# 06_LMS7002M_2_RF.net
KiCad netlist of a schematic drawn in Altium Designer
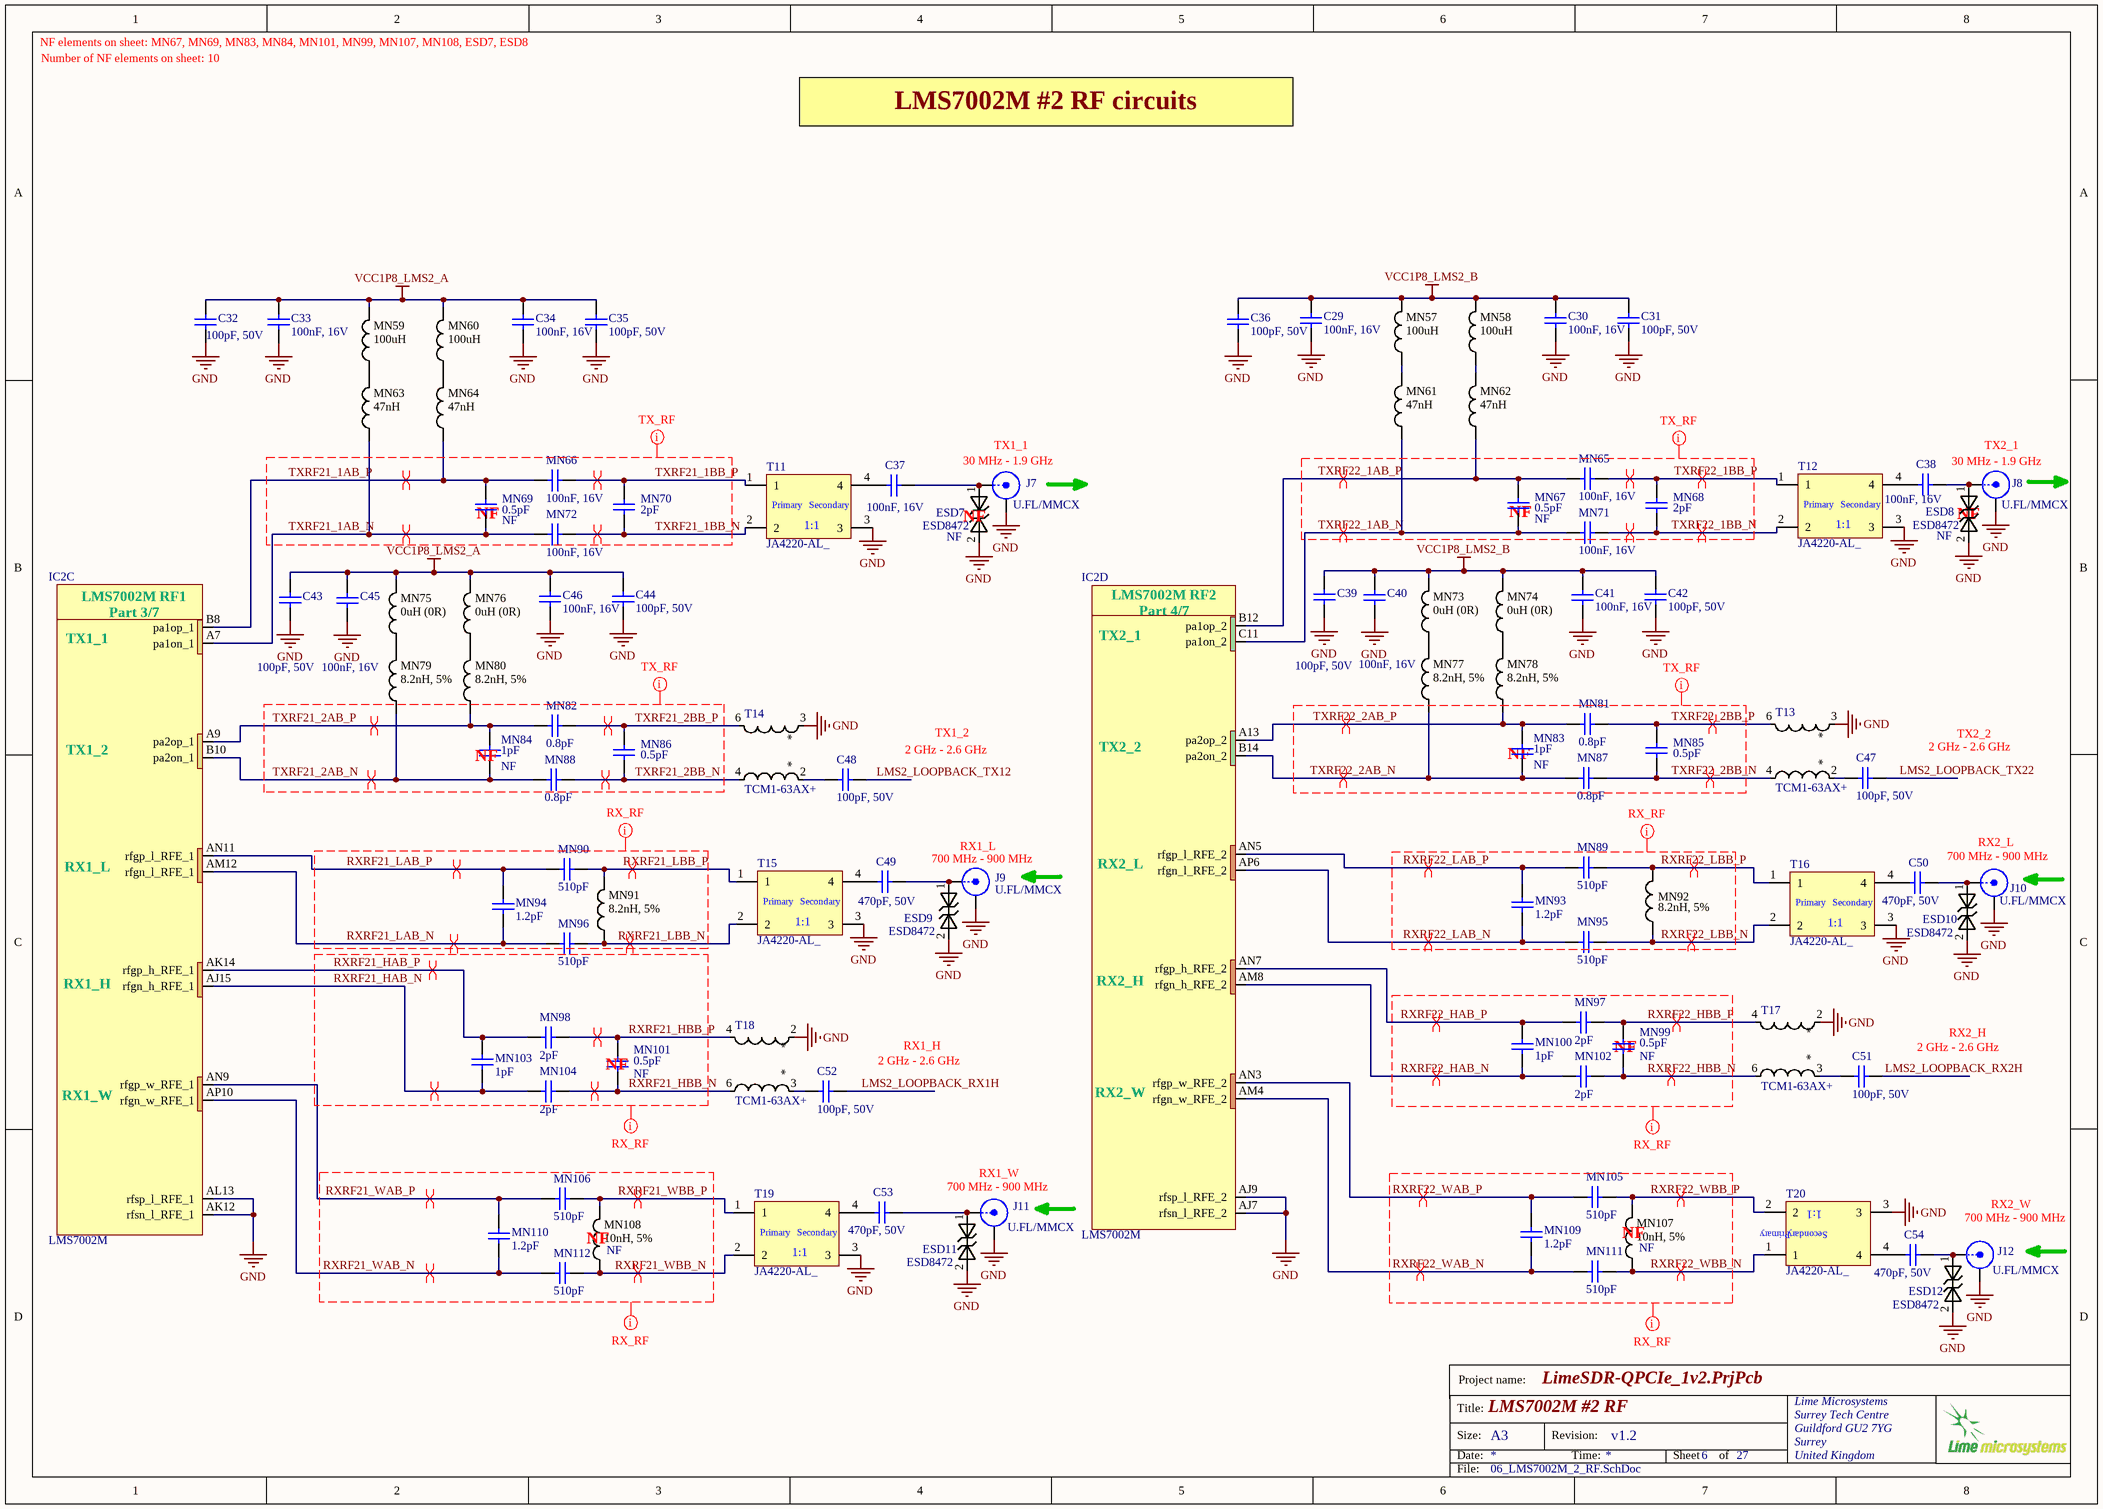
[diagram p0: 06_LMS7002M_2_RF.SchDoc]

(export (version "E")
  (design (tool "Eeschema 10.0.6"))
  (components
    (comp (ref "C29")
      (value "100nF, 16V")
      (footprint "CAP0402")
      (fields
        (field (name "MANUFACTURER") "Murata Electronics")
        (field (name "TOLERANCE") "10 %")
        (field (name "MANUFACTURER PART NUMBER") "GRM155R71C104KA88D")
      )
      (libsource (lib "LimeMicroAltiumLib_schLib") (part "Cap_0402"))
    )
    (comp (ref "C30")
      (value "100nF, 16V")
      (footprint "CAP0402")
      (fields
        (field (name "MANUFACTURER") "Murata Electronics")
        (field (name "TOLERANCE") "10 %")
        (field (name "MANUFACTURER PART NUMBER") "GRM155R71C104KA88D")
      )
      (libsource (lib "LimeMicroAltiumLib_schLib") (part "Cap_0402"))
    )
    (comp (ref "C31")
      (value "100pF, 50V")
      (footprint "CAP0402")
      (fields (field (name "MANUFACTURER") "Yageo") (field (name "TOLERANCE") "±5%"))
      (libsource (lib "LimeMicroAltiumLib_schLib") (part "Cap_0402"))
    )
    (comp (ref "C32")
      (value "100pF, 50V")
      (footprint "CAP0402")
      (fields (field (name "MANUFACTURER") "Yageo") (field (name "TOLERANCE") "±5%"))
      (libsource (lib "LimeMicroAltiumLib_schLib") (part "Cap_0402"))
    )
    (comp (ref "C33")
      (value "100nF, 16V")
      (footprint "CAP0402")
      (fields
        (field (name "MANUFACTURER") "Murata Electronics")
        (field (name "TOLERANCE") "10 %")
        (field (name "MANUFACTURER PART NUMBER") "GRM155R71C104KA88D")
      )
      (libsource (lib "LimeMicroAltiumLib_schLib") (part "Cap_0402"))
    )
    (comp (ref "C34")
      (value "100nF, 16V")
      (footprint "CAP0402")
      (fields
        (field (name "MANUFACTURER") "Murata Electronics")
        (field (name "TOLERANCE") "10 %")
        (field (name "MANUFACTURER PART NUMBER") "GRM155R71C104KA88D")
      )
      (libsource (lib "LimeMicroAltiumLib_schLib") (part "Cap_0402"))
    )
    (comp (ref "C35")
      (value "100pF, 50V")
      (footprint "CAP0402")
      (fields (field (name "MANUFACTURER") "Yageo") (field (name "TOLERANCE") "±5%"))
      (libsource (lib "LimeMicroAltiumLib_schLib") (part "Cap_0402"))
    )
    (comp (ref "C36")
      (value "100pF, 50V")
      (footprint "CAP0402")
      (fields (field (name "MANUFACTURER") "Yageo") (field (name "TOLERANCE") "±5%"))
      (libsource (lib "LimeMicroAltiumLib_schLib") (part "Cap_0402"))
    )
    (comp (ref "C37")
      (value "100nF, 16V")
      (footprint "CAP0402")
      (fields
        (field (name "MANUFACTURER") "Murata Electronics")
        (field (name "TOLERANCE") "10 %")
        (field (name "MANUFACTURER PART NUMBER") "GRM155R71C104KA88D")
      )
      (libsource (lib "LimeMicroAltiumLib_schLib") (part "Cap_0402"))
    )
    (comp (ref "C38")
      (value "100nF, 16V")
      (footprint "CAP0402")
      (fields
        (field (name "MANUFACTURER") "Murata Electronics")
        (field (name "TOLERANCE") "10 %")
        (field (name "MANUFACTURER PART NUMBER") "GRM155R71C104KA88D")
      )
      (libsource (lib "LimeMicroAltiumLib_schLib") (part "Cap_0402"))
    )
    (comp (ref "C39")
      (value "100pF, 50V")
      (footprint "CAP0402")
      (fields (field (name "MANUFACTURER") "Yageo") (field (name "TOLERANCE") "±5%"))
      (libsource (lib "LimeMicroAltiumLib_schLib") (part "Cap_0402"))
    )
    (comp (ref "C40")
      (value "100nF, 16V")
      (footprint "CAP0402")
      (fields
        (field (name "MANUFACTURER") "Murata Electronics")
        (field (name "TOLERANCE") "10 %")
        (field (name "MANUFACTURER PART NUMBER") "GRM155R71C104KA88D")
      )
      (libsource (lib "LimeMicroAltiumLib_schLib") (part "Cap_0402"))
    )
    (comp (ref "C41")
      (value "100nF, 16V")
      (footprint "CAP0402")
      (fields
        (field (name "MANUFACTURER") "Murata Electronics")
        (field (name "TOLERANCE") "10 %")
        (field (name "MANUFACTURER PART NUMBER") "GRM155R71C104KA88D")
      )
      (libsource (lib "LimeMicroAltiumLib_schLib") (part "Cap_0402"))
    )
    (comp (ref "C42")
      (value "100pF, 50V")
      (footprint "CAP0402")
      (fields (field (name "MANUFACTURER") "Yageo") (field (name "TOLERANCE") "±5%"))
      (libsource (lib "LimeMicroAltiumLib_schLib") (part "Cap_0402"))
    )
    (comp (ref "C43")
      (value "100pF, 50V")
      (footprint "CAP0402")
      (fields (field (name "MANUFACTURER") "Yageo") (field (name "TOLERANCE") "±5%"))
      (libsource (lib "LimeMicroAltiumLib_schLib") (part "Cap_0402"))
    )
    (comp (ref "C44")
      (value "100pF, 50V")
      (footprint "CAP0402")
      (fields (field (name "MANUFACTURER") "Yageo") (field (name "TOLERANCE") "±5%"))
      (libsource (lib "LimeMicroAltiumLib_schLib") (part "Cap_0402"))
    )
    (comp (ref "C45")
      (value "100nF, 16V")
      (footprint "CAP0402")
      (fields
        (field (name "MANUFACTURER") "Murata Electronics")
        (field (name "TOLERANCE") "10 %")
        (field (name "MANUFACTURER PART NUMBER") "GRM155R71C104KA88D")
      )
      (libsource (lib "LimeMicroAltiumLib_schLib") (part "Cap_0402"))
    )
    (comp (ref "C46")
      (value "100nF, 16V")
      (footprint "CAP0402")
      (fields
        (field (name "MANUFACTURER") "Murata Electronics")
        (field (name "TOLERANCE") "10 %")
        (field (name "MANUFACTURER PART NUMBER") "GRM155R71C104KA88D")
      )
      (libsource (lib "LimeMicroAltiumLib_schLib") (part "Cap_0402"))
    )
    (comp (ref "C47")
      (value "100pF, 50V")
      (footprint "CAP0402")
      (fields (field (name "TOLERANCE") "±5%") (field (name "MANUFACTURER") "Yageo"))
      (libsource (lib "LimeMicroAltiumLib_schLib") (part "Cap_0402"))
    )
    (comp (ref "C48")
      (value "100pF, 50V")
      (footprint "CAP0402")
      (fields (field (name "TOLERANCE") "±5%") (field (name "MANUFACTURER") "Yageo"))
      (libsource (lib "LimeMicroAltiumLib_schLib") (part "Cap_0402"))
    )
    (comp (ref "C49")
      (value "470pF, 50V")
      (footprint "CAP0402")
      (fields
        (field (name "MANUFACTURER PART NUMBER") "C1005C0G1H471J050BA")
        (field (name "TOLERANCE") "±5%")
        (field (name "MANUFACTURER") "TDK Corporation")
      )
      (libsource (lib "LimeMicroAltiumLib_schLib") (part "Cap_0402"))
    )
    (comp (ref "C50")
      (value "470pF, 50V")
      (footprint "CAP0402")
      (fields
        (field (name "MANUFACTURER PART NUMBER") "C1005C0G1H471J050BA")
        (field (name "TOLERANCE") "±5%")
        (field (name "MANUFACTURER") "TDK Corporation")
      )
      (libsource (lib "LimeMicroAltiumLib_schLib") (part "Cap_0402"))
    )
    (comp (ref "C51")
      (value "100pF, 50V")
      (footprint "CAP0402")
      (fields (field (name "TOLERANCE") "±5%") (field (name "MANUFACTURER") "Yageo"))
      (libsource (lib "LimeMicroAltiumLib_schLib") (part "Cap_0402"))
    )
    (comp (ref "C52")
      (value "100pF, 50V")
      (footprint "CAP0402")
      (fields (field (name "TOLERANCE") "±5%") (field (name "MANUFACTURER") "Yageo"))
      (libsource (lib "LimeMicroAltiumLib_schLib") (part "Cap_0402"))
    )
    (comp (ref "C53")
      (value "470pF, 50V")
      (footprint "CAP0402")
      (fields
        (field (name "MANUFACTURER PART NUMBER") "C1005C0G1H471J050BA")
        (field (name "TOLERANCE") "±5%")
        (field (name "MANUFACTURER") "TDK Corporation")
      )
      (libsource (lib "LimeMicroAltiumLib_schLib") (part "Cap_0402"))
    )
    (comp (ref "C54")
      (value "470pF, 50V")
      (footprint "CAP0402")
      (fields
        (field (name "MANUFACTURER PART NUMBER") "C1005C0G1H471J050BA")
        (field (name "TOLERANCE") "±5%")
        (field (name "MANUFACTURER") "TDK Corporation")
      )
      (libsource (lib "LimeMicroAltiumLib_schLib") (part "Cap_0402"))
    )
    (comp (ref "ESD7")
      (value "ESD8472")
      (footprint "ESD8472_X3DFN2")
      (fields
        (field (name "MANUFACTURER") "ON Semiconductor")
        (field (name "MANUFACTURER PART NUMBER") "ESD8472MUT5G")
        (field (name "ASSEMBLY INFO") "NF")
      )
      (libsource (lib "LimeMicroAltiumLib_schLib") (part "ESD8472"))
    )
    (comp (ref "ESD8")
      (value "ESD8472")
      (footprint "ESD8472_X3DFN2")
      (fields
        (field (name "MANUFACTURER") "ON Semiconductor")
        (field (name "MANUFACTURER PART NUMBER") "ESD8472MUT5G")
        (field (name "ASSEMBLY INFO") "NF")
      )
      (libsource (lib "LimeMicroAltiumLib_schLib") (part "ESD8472"))
    )
    (comp (ref "ESD9")
      (value "ESD8472")
      (footprint "ESD8472_X3DFN2")
      (fields
        (field (name "MANUFACTURER") "ON Semiconductor")
        (field (name "MANUFACTURER PART NUMBER") "ESD8472MUT5G")
      )
      (libsource (lib "LimeMicroAltiumLib_schLib") (part "ESD8472"))
    )
    (comp (ref "ESD10")
      (value "ESD8472")
      (footprint "ESD8472_X3DFN2")
      (fields
        (field (name "MANUFACTURER") "ON Semiconductor")
        (field (name "MANUFACTURER PART NUMBER") "ESD8472MUT5G")
      )
      (libsource (lib "LimeMicroAltiumLib_schLib") (part "ESD8472"))
    )
    (comp (ref "ESD11")
      (value "ESD8472")
      (footprint "ESD8472_X3DFN2")
      (fields
        (field (name "MANUFACTURER") "ON Semiconductor")
        (field (name "MANUFACTURER PART NUMBER") "ESD8472MUT5G")
      )
      (libsource (lib "LimeMicroAltiumLib_schLib") (part "ESD8472"))
    )
    (comp (ref "ESD12")
      (value "ESD8472")
      (footprint "ESD8472_X3DFN2")
      (fields
        (field (name "MANUFACTURER") "ON Semiconductor")
        (field (name "MANUFACTURER PART NUMBER") "ESD8472MUT5G")
      )
      (libsource (lib "LimeMicroAltiumLib_schLib") (part "ESD8472"))
    )
    (comp (ref "IC2")
      (value "LMS7002M")
      (footprint "LMS7002M_v4")
      (description "Schematic symbol revision 3. Default footprint - 0.31mm pad")
      (fields (field (name "MANUFACTURER") "Lime Microsystems"))
      (libsource (lib "LimeMicroAltiumLib_schLib") (part "LMS7002Mr3"))
    )
    (comp (ref "J7")
      (value "U.FL/MMCX")
      (footprint "MMCX_UFL_conn_u")
      (description "CONN UMC RCPT STR 50 OHM SMD")
      (fields (field (name "MANUFACTURER") "Molex, LLC"))
      (libsource (lib "LimeMicroAltiumLib_schLib") (part "RF_IF_connector"))
    )
    (comp (ref "J8")
      (value "U.FL/MMCX")
      (footprint "MMCX_UFL_conn_u")
      (description "CONN UMC RCPT STR 50 OHM SMD")
      (fields (field (name "MANUFACTURER") "Molex, LLC"))
      (libsource (lib "LimeMicroAltiumLib_schLib") (part "RF_IF_connector"))
    )
    (comp (ref "J9")
      (value "U.FL/MMCX")
      (footprint "MMCX_UFL_conn_u")
      (description "CONN UMC RCPT STR 50 OHM SMD")
      (fields (field (name "MANUFACTURER") "Molex, LLC"))
      (libsource (lib "LimeMicroAltiumLib_schLib") (part "RF_IF_connector"))
    )
    (comp (ref "J10")
      (value "U.FL/MMCX")
      (footprint "MMCX_UFL_conn_u")
      (description "CONN UMC RCPT STR 50 OHM SMD")
      (fields (field (name "MANUFACTURER") "Molex, LLC"))
      (libsource (lib "LimeMicroAltiumLib_schLib") (part "RF_IF_connector"))
    )
    (comp (ref "J11")
      (value "U.FL/MMCX")
      (footprint "MMCX_UFL_conn_u")
      (description "CONN UMC RCPT STR 50 OHM SMD")
      (fields (field (name "MANUFACTURER") "Molex, LLC"))
      (libsource (lib "LimeMicroAltiumLib_schLib") (part "RF_IF_connector"))
    )
    (comp (ref "J12")
      (value "U.FL/MMCX")
      (footprint "MMCX_UFL_conn_u")
      (description "CONN UMC RCPT STR 50 OHM SMD")
      (fields (field (name "MANUFACTURER") "Molex, LLC"))
      (libsource (lib "LimeMicroAltiumLib_schLib") (part "RF_IF_connector"))
    )
    (comp (ref "MN57")
      (value "100uH")
      (footprint "RES0805")
      (fields
        (field (name "TOLERANCE") "±10%")
        (field (name "MANUFACTURER") "TDK Corporation")
        (field (name "MANUFACTURER PART NUMBER") "MLF2012C101KT000")
      )
      (libsource (lib "LimeMicroAltiumLib_schLib") (part "Inductor_0603"))
    )
    (comp (ref "MN58")
      (value "100uH")
      (footprint "RES0805")
      (fields
        (field (name "TOLERANCE") "±10%")
        (field (name "MANUFACTURER") "TDK Corporation")
        (field (name "MANUFACTURER PART NUMBER") "MLF2012C101KT000")
      )
      (libsource (lib "LimeMicroAltiumLib_schLib") (part "Inductor_0603"))
    )
    (comp (ref "MN59")
      (value "100uH")
      (footprint "RES0805")
      (fields
        (field (name "TOLERANCE") "±10%")
        (field (name "MANUFACTURER") "TDK Corporation")
        (field (name "MANUFACTURER PART NUMBER") "MLF2012C101KT000")
      )
      (libsource (lib "LimeMicroAltiumLib_schLib") (part "Inductor_0603"))
    )
    (comp (ref "MN60")
      (value "100uH")
      (footprint "RES0805")
      (fields
        (field (name "TOLERANCE") "±10%")
        (field (name "MANUFACTURER") "TDK Corporation")
        (field (name "MANUFACTURER PART NUMBER") "MLF2012C101KT000")
      )
      (libsource (lib "LimeMicroAltiumLib_schLib") (part "Inductor_0603"))
    )
    (comp (ref "MN61")
      (value "47nH")
      (footprint "RES0402")
      (fields
        (field (name "MANUFACTURER") "COILCRAFT")
        (field (name "MANUFACTURER PART NUMBER") "0402HP-47NXJLU")
      )
      (libsource (lib "LimeMicroAltiumLib_schLib") (part "Inductor_0603"))
    )
    (comp (ref "MN62")
      (value "47nH")
      (footprint "RES0402")
      (fields
        (field (name "MANUFACTURER") "COILCRAFT")
        (field (name "MANUFACTURER PART NUMBER") "0402HP-47NXJLU")
      )
      (libsource (lib "LimeMicroAltiumLib_schLib") (part "Inductor_0603"))
    )
    (comp (ref "MN63")
      (value "47nH")
      (footprint "RES0402")
      (fields
        (field (name "MANUFACTURER") "COILCRAFT")
        (field (name "MANUFACTURER PART NUMBER") "0402HP-47NXJLU")
      )
      (libsource (lib "LimeMicroAltiumLib_schLib") (part "Inductor_0603"))
    )
    (comp (ref "MN64")
      (value "47nH")
      (footprint "RES0402")
      (fields
        (field (name "MANUFACTURER") "COILCRAFT")
        (field (name "MANUFACTURER PART NUMBER") "0402HP-47NXJLU")
      )
      (libsource (lib "LimeMicroAltiumLib_schLib") (part "Inductor_0603"))
    )
    (comp (ref "MN65")
      (value "100nF, 16V")
      (footprint "CAP0402")
      (fields
        (field (name "MANUFACTURER") "Murata Electronics")
        (field (name "TOLERANCE") "10 %")
        (field (name "MANUFACTURER PART NUMBER") "GRM155R71C104KA88D")
      )
      (libsource (lib "LimeMicroAltiumLib_schLib") (part "Cap_0402"))
    )
    (comp (ref "MN66")
      (value "100nF, 16V")
      (footprint "CAP0402")
      (fields
        (field (name "MANUFACTURER") "Murata Electronics")
        (field (name "TOLERANCE") "10 %")
        (field (name "MANUFACTURER PART NUMBER") "GRM155R71C104KA88D")
      )
      (libsource (lib "LimeMicroAltiumLib_schLib") (part "Cap_0402"))
    )
    (comp (ref "MN67")
      (value "0.5pF")
      (footprint "CAP0402")
      (fields
        (field (name "ASSEMBLY INFO") "NF")
        (field (name "TOLERANCE") "±0.25pF")
        (field (name "MANUFACTURER") "Yageo")
      )
      (libsource (lib "LimeMicroAltiumLib_schLib") (part "Cap_0402"))
    )
    (comp (ref "MN68")
      (value "2pF")
      (footprint "CAP0402")
      (fields (field (name "MANUFACTURER") "AVX"))
      (libsource (lib "LimeMicroAltiumLib_schLib") (part "Cap_0402"))
    )
    (comp (ref "MN69")
      (value "0.5pF")
      (footprint "CAP0402")
      (fields
        (field (name "ASSEMBLY INFO") "NF")
        (field (name "TOLERANCE") "±0.25pF")
        (field (name "MANUFACTURER") "Yageo")
      )
      (libsource (lib "LimeMicroAltiumLib_schLib") (part "Cap_0402"))
    )
    (comp (ref "MN70")
      (value "2pF")
      (footprint "CAP0402")
      (fields (field (name "MANUFACTURER") "AVX"))
      (libsource (lib "LimeMicroAltiumLib_schLib") (part "Cap_0402"))
    )
    (comp (ref "MN71")
      (value "100nF, 16V")
      (footprint "CAP0402")
      (fields
        (field (name "MANUFACTURER") "Murata Electronics")
        (field (name "TOLERANCE") "10 %")
        (field (name "MANUFACTURER PART NUMBER") "GRM155R71C104KA88D")
      )
      (libsource (lib "LimeMicroAltiumLib_schLib") (part "Cap_0402"))
    )
    (comp (ref "MN72")
      (value "100nF, 16V")
      (footprint "CAP0402")
      (fields
        (field (name "MANUFACTURER") "Murata Electronics")
        (field (name "TOLERANCE") "10 %")
        (field (name "MANUFACTURER PART NUMBER") "GRM155R71C104KA88D")
      )
      (libsource (lib "LimeMicroAltiumLib_schLib") (part "Cap_0402"))
    )
    (comp (ref "MN73")
      (value "0uH (0R)")
      (footprint "RES0805")
      (fields (field (name "MANUFACTURER") "BOURNS"))
      (libsource (lib "LimeMicroAltiumLib_schLib") (part "Inductor_0603"))
    )
    (comp (ref "MN74")
      (value "0uH (0R)")
      (footprint "RES0805")
      (fields (field (name "MANUFACTURER") "BOURNS"))
      (libsource (lib "LimeMicroAltiumLib_schLib") (part "Inductor_0603"))
    )
    (comp (ref "MN75")
      (value "0uH (0R)")
      (footprint "RES0805")
      (fields (field (name "MANUFACTURER") "BOURNS"))
      (libsource (lib "LimeMicroAltiumLib_schLib") (part "Inductor_0603"))
    )
    (comp (ref "MN76")
      (value "0uH (0R)")
      (footprint "RES0805")
      (fields (field (name "MANUFACTURER") "BOURNS"))
      (libsource (lib "LimeMicroAltiumLib_schLib") (part "Inductor_0603"))
    )
    (comp (ref "MN77")
      (value "8.2nH, 5%")
      (footprint "RES0402")
      (fields (field (name "MANUFACTURER") "COILCRAFT"))
      (libsource (lib "LimeMicroAltiumLib_schLib") (part "Inductor_0603"))
    )
    (comp (ref "MN78")
      (value "8.2nH, 5%")
      (footprint "RES0402")
      (fields (field (name "MANUFACTURER") "COILCRAFT"))
      (libsource (lib "LimeMicroAltiumLib_schLib") (part "Inductor_0603"))
    )
    (comp (ref "MN79")
      (value "8.2nH, 5%")
      (footprint "RES0402")
      (fields (field (name "MANUFACTURER") "COILCRAFT"))
      (libsource (lib "LimeMicroAltiumLib_schLib") (part "Inductor_0603"))
    )
    (comp (ref "MN80")
      (value "8.2nH, 5%")
      (footprint "RES0402")
      (fields (field (name "MANUFACTURER") "COILCRAFT"))
      (libsource (lib "LimeMicroAltiumLib_schLib") (part "Inductor_0603"))
    )
    (comp (ref "MN81")
      (value "0.8pF")
      (footprint "CAP0402")
      (fields
        (field (name "TOLERANCE") "±0.1pF")
        (field (name "MANUFACTURER") "Murata Electronics North America")
      )
      (libsource (lib "LimeMicroAltiumLib_schLib") (part "Cap_0402"))
    )
    (comp (ref "MN82")
      (value "0.8pF")
      (footprint "CAP0402")
      (fields
        (field (name "TOLERANCE") "±0.1pF")
        (field (name "MANUFACTURER") "Murata Electronics North America")
      )
      (libsource (lib "LimeMicroAltiumLib_schLib") (part "Cap_0402"))
    )
    (comp (ref "MN83")
      (value "1pF")
      (footprint "CAP0402")
      (fields
        (field (name "ASSEMBLY INFO") "NF")
        (field (name "MANUFACTURER") "TDK Corporation")
        (field (name "TOLERANCE") "±0.1pF")
      )
      (libsource (lib "LimeMicroAltiumLib_schLib") (part "Cap_0402"))
    )
    (comp (ref "MN84")
      (value "1pF")
      (footprint "CAP0402")
      (fields
        (field (name "ASSEMBLY INFO") "NF")
        (field (name "MANUFACTURER") "TDK Corporation")
        (field (name "TOLERANCE") "±0.1pF")
      )
      (libsource (lib "LimeMicroAltiumLib_schLib") (part "Cap_0402"))
    )
    (comp (ref "MN85")
      (value "0.5pF")
      (footprint "CAP0402")
      (fields (field (name "TOLERANCE") "±0.25pF") (field (name "MANUFACTURER") "Yageo"))
      (libsource (lib "LimeMicroAltiumLib_schLib") (part "Cap_0402"))
    )
    (comp (ref "MN86")
      (value "0.5pF")
      (footprint "CAP0402")
      (fields (field (name "TOLERANCE") "±0.25pF") (field (name "MANUFACTURER") "Yageo"))
      (libsource (lib "LimeMicroAltiumLib_schLib") (part "Cap_0402"))
    )
    (comp (ref "MN87")
      (value "0.8pF")
      (footprint "CAP0402")
      (fields
        (field (name "TOLERANCE") "±0.1pF")
        (field (name "MANUFACTURER") "Murata Electronics North America")
      )
      (libsource (lib "LimeMicroAltiumLib_schLib") (part "Cap_0402"))
    )
    (comp (ref "MN88")
      (value "0.8pF")
      (footprint "CAP0402")
      (fields
        (field (name "TOLERANCE") "±0.1pF")
        (field (name "MANUFACTURER") "Murata Electronics North America")
      )
      (libsource (lib "LimeMicroAltiumLib_schLib") (part "Cap_0402"))
    )
    (comp (ref "MN89")
      (value "510pF")
      (footprint "CAP0402")
      (fields
        (field (name "TOLERANCE") "±5%")
        (field (name "MANUFACTURER") "Murata Electronics North America")
      )
      (libsource (lib "LimeMicroAltiumLib_schLib") (part "Cap_0402"))
    )
    (comp (ref "MN90")
      (value "510pF")
      (footprint "CAP0402")
      (fields
        (field (name "TOLERANCE") "±5%")
        (field (name "MANUFACTURER") "Murata Electronics North America")
      )
      (libsource (lib "LimeMicroAltiumLib_schLib") (part "Cap_0402"))
    )
    (comp (ref "MN91")
      (value "8.2nH, 5%")
      (footprint "RES0402")
      (fields (field (name "MANUFACTURER") "COILCRAFT"))
      (libsource (lib "LimeMicroAltiumLib_schLib") (part "Inductor_0603"))
    )
    (comp (ref "MN92")
      (value "8.2nH, 5%")
      (footprint "RES0402")
      (fields (field (name "MANUFACTURER") "COILCRAFT"))
      (libsource (lib "LimeMicroAltiumLib_schLib") (part "Inductor_0603"))
    )
    (comp (ref "MN93")
      (value "1.2pF")
      (footprint "CAP0402")
      (fields
        (field (name "MANUFACTURER") "Murata Electronics North America")
        (field (name "TOLERANCE") "±0.25pF")
      )
      (libsource (lib "LimeMicroAltiumLib_schLib") (part "Cap_0402"))
    )
    (comp (ref "MN94")
      (value "1.2pF")
      (footprint "CAP0402")
      (fields
        (field (name "MANUFACTURER") "Murata Electronics North America")
        (field (name "TOLERANCE") "±0.25pF")
      )
      (libsource (lib "LimeMicroAltiumLib_schLib") (part "Cap_0402"))
    )
    (comp (ref "MN95")
      (value "510pF")
      (footprint "CAP0402")
      (fields
        (field (name "TOLERANCE") "±5%")
        (field (name "MANUFACTURER") "Murata Electronics North America")
      )
      (libsource (lib "LimeMicroAltiumLib_schLib") (part "Cap_0402"))
    )
    (comp (ref "MN96")
      (value "510pF")
      (footprint "CAP0402")
      (fields
        (field (name "TOLERANCE") "±5%")
        (field (name "MANUFACTURER") "Murata Electronics North America")
      )
      (libsource (lib "LimeMicroAltiumLib_schLib") (part "Cap_0402"))
    )
    (comp (ref "MN97")
      (value "2pF")
      (footprint "CAP0402")
      (fields (field (name "MANUFACTURER") "AVX"))
      (libsource (lib "LimeMicroAltiumLib_schLib") (part "Cap_0402"))
    )
    (comp (ref "MN98")
      (value "2pF")
      (footprint "CAP0402")
      (fields (field (name "MANUFACTURER") "AVX"))
      (libsource (lib "LimeMicroAltiumLib_schLib") (part "Cap_0402"))
    )
    (comp (ref "MN99")
      (value "0.5pF")
      (footprint "CAP0402")
      (fields
        (field (name "ASSEMBLY INFO") "NF")
        (field (name "TOLERANCE") "±0.25pF")
        (field (name "MANUFACTURER") "Yageo")
      )
      (libsource (lib "LimeMicroAltiumLib_schLib") (part "Cap_0402"))
    )
    (comp (ref "MN100")
      (value "1pF")
      (footprint "CAP0402")
      (fields (field (name "MANUFACTURER") "TDK Corporation") (field (name "TOLERANCE") "±0.1pF"))
      (libsource (lib "LimeMicroAltiumLib_schLib") (part "Cap_0402"))
    )
    (comp (ref "MN101")
      (value "0.5pF")
      (footprint "CAP0402")
      (fields
        (field (name "ASSEMBLY INFO") "NF")
        (field (name "TOLERANCE") "±0.25pF")
        (field (name "MANUFACTURER") "Yageo")
      )
      (libsource (lib "LimeMicroAltiumLib_schLib") (part "Cap_0402"))
    )
    (comp (ref "MN102")
      (value "2pF")
      (footprint "CAP0402")
      (fields (field (name "MANUFACTURER") "AVX"))
      (libsource (lib "LimeMicroAltiumLib_schLib") (part "Cap_0402"))
    )
    (comp (ref "MN103")
      (value "1pF")
      (footprint "CAP0402")
      (fields (field (name "MANUFACTURER") "TDK Corporation") (field (name "TOLERANCE") "±0.1pF"))
      (libsource (lib "LimeMicroAltiumLib_schLib") (part "Cap_0402"))
    )
    (comp (ref "MN104")
      (value "2pF")
      (footprint "CAP0402")
      (fields (field (name "MANUFACTURER") "AVX"))
      (libsource (lib "LimeMicroAltiumLib_schLib") (part "Cap_0402"))
    )
    (comp (ref "MN105")
      (value "510pF")
      (footprint "CAP0402")
      (fields
        (field (name "TOLERANCE") "±5%")
        (field (name "MANUFACTURER") "Murata Electronics North America")
      )
      (libsource (lib "LimeMicroAltiumLib_schLib") (part "Cap_0402"))
    )
    (comp (ref "MN106")
      (value "510pF")
      (footprint "CAP0402")
      (fields
        (field (name "TOLERANCE") "±5%")
        (field (name "MANUFACTURER") "Murata Electronics North America")
      )
      (libsource (lib "LimeMicroAltiumLib_schLib") (part "Cap_0402"))
    )
    (comp (ref "MN107")
      (value "10nH, 5%")
      (footprint "RES0402")
      (fields (field (name "MANUFACTURER") "COILCRAFT") (field (name "ASSEMBLY INFO") "NF"))
      (libsource (lib "LimeMicroAltiumLib_schLib") (part "Inductor_0603"))
    )
    (comp (ref "MN108")
      (value "10nH, 5%")
      (footprint "RES0402")
      (fields (field (name "MANUFACTURER") "COILCRAFT") (field (name "ASSEMBLY INFO") "NF"))
      (libsource (lib "LimeMicroAltiumLib_schLib") (part "Inductor_0603"))
    )
    (comp (ref "MN109")
      (value "1.2pF")
      (footprint "CAP0402")
      (fields
        (field (name "MANUFACTURER") "Murata Electronics North America")
        (field (name "TOLERANCE") "±0.25pF")
      )
      (libsource (lib "LimeMicroAltiumLib_schLib") (part "Cap_0402"))
    )
    (comp (ref "MN110")
      (value "1.2pF")
      (footprint "CAP0402")
      (fields
        (field (name "MANUFACTURER") "Murata Electronics North America")
        (field (name "TOLERANCE") "±0.25pF")
      )
      (libsource (lib "LimeMicroAltiumLib_schLib") (part "Cap_0402"))
    )
    (comp (ref "MN111")
      (value "510pF")
      (footprint "CAP0402")
      (fields
        (field (name "TOLERANCE") "±5%")
        (field (name "MANUFACTURER") "Murata Electronics North America")
      )
      (libsource (lib "LimeMicroAltiumLib_schLib") (part "Cap_0402"))
    )
    (comp (ref "MN112")
      (value "510pF")
      (footprint "CAP0402")
      (fields
        (field (name "TOLERANCE") "±5%")
        (field (name "MANUFACTURER") "Murata Electronics North America")
      )
      (libsource (lib "LimeMicroAltiumLib_schLib") (part "Cap_0402"))
    )
    (comp (ref "T11")
      (value "JA4220-AL_")
      (footprint "JA4220-AL_")
      (fields (field (name "MANUFACTURER") "Coilcraft"))
      (libsource (lib "LimeMicroAltiumLib_schLib") (part "JA4220-AL_"))
    )
    (comp (ref "T12")
      (value "JA4220-AL_")
      (footprint "JA4220-AL_")
      (fields (field (name "MANUFACTURER") "Coilcraft"))
      (libsource (lib "LimeMicroAltiumLib_schLib") (part "JA4220-AL_"))
    )
    (comp (ref "T13")
      (value "TCM1-63AX+")
      (footprint "TCM1-63AX+_v2")
      (fields (field (name "MANUFACTURER") "Mini-circuits"))
      (libsource (lib "") (part "Balun_v2_1"))
    )
    (comp (ref "T14")
      (value "TCM1-63AX+")
      (footprint "TCM1-63AX+_v2")
      (fields (field (name "MANUFACTURER") "Mini-circuits"))
      (libsource (lib "") (part "Balun_v2_1"))
    )
    (comp (ref "T15")
      (value "JA4220-AL_")
      (footprint "JA4220-AL_")
      (fields (field (name "MANUFACTURER") "Coilcraft"))
      (libsource (lib "LimeMicroAltiumLib_schLib") (part "JA4220-AL_"))
    )
    (comp (ref "T16")
      (value "JA4220-AL_")
      (footprint "JA4220-AL_")
      (fields (field (name "MANUFACTURER") "Coilcraft"))
      (libsource (lib "LimeMicroAltiumLib_schLib") (part "JA4220-AL_"))
    )
    (comp (ref "T17")
      (value "TCM1-63AX+")
      (footprint "TCM1-63AX+_v2")
      (fields (field (name "MANUFACTURER") "Mini-circuits"))
      (libsource (lib "LimeMicroAltiumLib_schLib") (part "Balun_v2"))
    )
    (comp (ref "T18")
      (value "TCM1-63AX+")
      (footprint "TCM1-63AX+_v2")
      (fields (field (name "MANUFACTURER") "Mini-circuits"))
      (libsource (lib "LimeMicroAltiumLib_schLib") (part "Balun_v2"))
    )
    (comp (ref "T19")
      (value "JA4220-AL_")
      (footprint "JA4220-AL_")
      (fields (field (name "MANUFACTURER") "Coilcraft"))
      (libsource (lib "LimeMicroAltiumLib_schLib") (part "JA4220-AL_"))
    )
    (comp (ref "T20")
      (value "JA4220-AL_")
      (footprint "JA4220-AL_")
      (fields (field (name "MANUFACTURER") "Coilcraft"))
      (libsource (lib "") (part "JA4220-AL__1"))
    )
  )
  (nets
    (net (code "1") (name "/LMS2_LOOPBACK_RX1H") (class "Default")
      (node (ref "C52") (pin "1") (pinfunction "1_1") (pintype "passive"))
    )
    (net (code "2") (name "/LMS2_LOOPBACK_RX2H") (class "Default")
      (node (ref "C51") (pin "1") (pinfunction "1_1") (pintype "passive"))
    )
    (net (code "3") (name "/LMS2_LOOPBACK_TX12") (class "Default")
      (node (ref "C48") (pin "1") (pinfunction "1_1") (pintype "passive"))
    )
    (net (code "4") (name "/LMS2_LOOPBACK_TX22") (class "Default")
      (node (ref "C47") (pin "1") (pinfunction "1_1") (pintype "passive"))
    )
    (net (code "5") (name "/RXRF21_HAB_N") (class "Default")
      (node (ref "IC2") (pin "AJ15") (pinfunction "rfgn_h_RFE_1_AJ15") (pintype "passive"))
      (node (ref "MN103") (pin "1") (pinfunction "1_1") (pintype "passive"))
      (node (ref "MN104") (pin "2") (pinfunction "2_2") (pintype "passive"))
    )
    (net (code "6") (name "/RXRF21_HAB_P") (class "Default")
      (node (ref "IC2") (pin "AK14") (pinfunction "rfgp_h_RFE_1_AK14") (pintype "passive"))
      (node (ref "MN103") (pin "2") (pinfunction "2_2") (pintype "passive"))
      (node (ref "MN98") (pin "2") (pinfunction "2_2") (pintype "passive"))
    )
    (net (code "7") (name "/RXRF21_HBB_N") (class "Default")
      (node (ref "MN101") (pin "1") (pinfunction "1_1") (pintype "passive"))
      (node (ref "MN104") (pin "1") (pinfunction "1_1") (pintype "passive"))
      (node (ref "T18") (pin "6") (pinfunction "6_6") (pintype "passive"))
    )
    (net (code "8") (name "/RXRF21_HBB_P") (class "Default")
      (node (ref "MN101") (pin "2") (pinfunction "2_2") (pintype "passive"))
      (node (ref "MN98") (pin "1") (pinfunction "1_1") (pintype "passive"))
      (node (ref "T18") (pin "4") (pinfunction "4_4") (pintype "passive"))
    )
    (net (code "9") (name "/RXRF21_LAB_N") (class "Default")
      (node (ref "IC2") (pin "AM12") (pinfunction "rfgn_l_RFE_1_AM12") (pintype "passive"))
      (node (ref "MN94") (pin "1") (pinfunction "1_1") (pintype "passive"))
      (node (ref "MN96") (pin "2") (pinfunction "2_2") (pintype "passive"))
    )
    (net (code "10") (name "/RXRF21_LAB_P") (class "Default")
      (node (ref "IC2") (pin "AN11") (pinfunction "rfgp_l_RFE_1_AN11") (pintype "passive"))
      (node (ref "MN90") (pin "2") (pinfunction "2_2") (pintype "passive"))
      (node (ref "MN94") (pin "2") (pinfunction "2_2") (pintype "passive"))
    )
    (net (code "11") (name "/RXRF21_LBB_N") (class "Default")
      (node (ref "MN91") (pin "1") (pinfunction "1_1") (pintype "passive"))
      (node (ref "MN96") (pin "1") (pinfunction "1_1") (pintype "passive"))
      (node (ref "T15") (pin "2") (pinfunction "2_2") (pintype "passive"))
    )
    (net (code "12") (name "/RXRF21_LBB_P") (class "Default")
      (node (ref "MN90") (pin "1") (pinfunction "1_1") (pintype "passive"))
      (node (ref "MN91") (pin "2") (pinfunction "2_2") (pintype "passive"))
      (node (ref "T15") (pin "1") (pinfunction "1_1") (pintype "passive"))
    )
    (net (code "13") (name "/RXRF21_WAB_N") (class "Default")
      (node (ref "IC2") (pin "AP10") (pinfunction "rfgn_w_RFE_1_AP10") (pintype "passive"))
      (node (ref "MN110") (pin "2") (pinfunction "2_2") (pintype "passive"))
      (node (ref "MN112") (pin "2") (pinfunction "2_2") (pintype "passive"))
    )
    (net (code "14") (name "/RXRF21_WAB_P") (class "Default")
      (node (ref "IC2") (pin "AN9") (pinfunction "rfgp_w_RFE_1_AN9") (pintype "passive"))
      (node (ref "MN106") (pin "2") (pinfunction "2_2") (pintype "passive"))
      (node (ref "MN110") (pin "1") (pinfunction "1_1") (pintype "passive"))
    )
    (net (code "15") (name "/RXRF21_WBB_N") (class "Default")
      (node (ref "MN108") (pin "1") (pinfunction "1_1") (pintype "passive"))
      (node (ref "MN112") (pin "1") (pinfunction "1_1") (pintype "passive"))
      (node (ref "T19") (pin "2") (pinfunction "2_2") (pintype "passive"))
    )
    (net (code "16") (name "/RXRF21_WBB_P") (class "Default")
      (node (ref "MN106") (pin "1") (pinfunction "1_1") (pintype "passive"))
      (node (ref "MN108") (pin "2") (pinfunction "2_2") (pintype "passive"))
      (node (ref "T19") (pin "1") (pinfunction "1_1") (pintype "passive"))
    )
    (net (code "17") (name "/RXRF22_HAB_N") (class "Default")
      (node (ref "IC2") (pin "AM8") (pinfunction "rfgn_h_RFE_2_AM8") (pintype "passive"))
      (node (ref "MN100") (pin "1") (pinfunction "1_1") (pintype "passive"))
      (node (ref "MN102") (pin "2") (pinfunction "2_2") (pintype "passive"))
    )
    (net (code "18") (name "/RXRF22_HAB_P") (class "Default")
      (node (ref "IC2") (pin "AN7") (pinfunction "rfgp_h_RFE_2_AN7") (pintype "passive"))
      (node (ref "MN100") (pin "2") (pinfunction "2_2") (pintype "passive"))
      (node (ref "MN97") (pin "2") (pinfunction "2_2") (pintype "passive"))
    )
    (net (code "19") (name "/RXRF22_HBB_N") (class "Default")
      (node (ref "MN102") (pin "1") (pinfunction "1_1") (pintype "passive"))
      (node (ref "MN99") (pin "1") (pinfunction "1_1") (pintype "passive"))
      (node (ref "T17") (pin "6") (pinfunction "6_6") (pintype "passive"))
    )
    (net (code "20") (name "/RXRF22_HBB_P") (class "Default")
      (node (ref "MN97") (pin "1") (pinfunction "1_1") (pintype "passive"))
      (node (ref "MN99") (pin "2") (pinfunction "2_2") (pintype "passive"))
      (node (ref "T17") (pin "4") (pinfunction "4_4") (pintype "passive"))
    )
    (net (code "21") (name "/RXRF22_LAB_N") (class "Default")
      (node (ref "IC2") (pin "AP6") (pinfunction "rfgn_l_RFE_2_AP6") (pintype "passive"))
      (node (ref "MN93") (pin "1") (pinfunction "1_1") (pintype "passive"))
      (node (ref "MN95") (pin "2") (pinfunction "2_2") (pintype "passive"))
    )
    (net (code "22") (name "/RXRF22_LAB_P") (class "Default")
      (node (ref "IC2") (pin "AN5") (pinfunction "rfgp_l_RFE_2_AN5") (pintype "passive"))
      (node (ref "MN89") (pin "2") (pinfunction "2_2") (pintype "passive"))
      (node (ref "MN93") (pin "2") (pinfunction "2_2") (pintype "passive"))
    )
    (net (code "23") (name "/RXRF22_LBB_N") (class "Default")
      (node (ref "MN92") (pin "1") (pinfunction "1_1") (pintype "passive"))
      (node (ref "MN95") (pin "1") (pinfunction "1_1") (pintype "passive"))
      (node (ref "T16") (pin "2") (pinfunction "2_2") (pintype "passive"))
    )
    (net (code "24") (name "/RXRF22_LBB_P") (class "Default")
      (node (ref "MN89") (pin "1") (pinfunction "1_1") (pintype "passive"))
      (node (ref "MN92") (pin "2") (pinfunction "2_2") (pintype "passive"))
      (node (ref "T16") (pin "1") (pinfunction "1_1") (pintype "passive"))
    )
    (net (code "25") (name "/RXRF22_WAB_N") (class "Default")
      (node (ref "IC2") (pin "AM4") (pinfunction "rfgn_w_RFE_2_AM4") (pintype "passive"))
      (node (ref "MN109") (pin "2") (pinfunction "2_2") (pintype "passive"))
      (node (ref "MN111") (pin "2") (pinfunction "2_2") (pintype "passive"))
    )
    (net (code "26") (name "/RXRF22_WAB_P") (class "Default")
      (node (ref "IC2") (pin "AN3") (pinfunction "rfgp_w_RFE_2_AN3") (pintype "passive"))
      (node (ref "MN105") (pin "2") (pinfunction "2_2") (pintype "passive"))
      (node (ref "MN109") (pin "1") (pinfunction "1_1") (pintype "passive"))
    )
    (net (code "27") (name "/RXRF22_WBB_N") (class "Default")
      (node (ref "MN107") (pin "1") (pinfunction "1_1") (pintype "passive"))
      (node (ref "MN111") (pin "1") (pinfunction "1_1") (pintype "passive"))
      (node (ref "T20") (pin "1") (pinfunction "1_1") (pintype "passive"))
    )
    (net (code "28") (name "/RXRF22_WBB_P") (class "Default")
      (node (ref "MN105") (pin "1") (pinfunction "1_1") (pintype "passive"))
      (node (ref "MN107") (pin "2") (pinfunction "2_2") (pintype "passive"))
      (node (ref "T20") (pin "2") (pinfunction "2_2") (pintype "passive"))
    )
    (net (code "29") (name "/TXRF21_1AB_N") (class "Default")
      (node (ref "IC2") (pin "A7") (pinfunction "pa1on_1_A7") (pintype "passive"))
      (node (ref "MN63") (pin "1") (pinfunction "1_1") (pintype "passive"))
      (node (ref "MN69") (pin "1") (pinfunction "1_1") (pintype "passive"))
      (node (ref "MN72") (pin "1") (pinfunction "1_1") (pintype "passive"))
    )
    (net (code "30") (name "/TXRF21_1AB_P") (class "Default")
      (node (ref "IC2") (pin "B8") (pinfunction "pa1op_1_B8") (pintype "passive"))
      (node (ref "MN64") (pin "1") (pinfunction "1_1") (pintype "passive"))
      (node (ref "MN66") (pin "2") (pinfunction "2_2") (pintype "passive"))
      (node (ref "MN69") (pin "2") (pinfunction "2_2") (pintype "passive"))
    )
    (net (code "31") (name "/TXRF21_1BB_N") (class "Default")
      (node (ref "MN70") (pin "1") (pinfunction "1_1") (pintype "passive"))
      (node (ref "MN72") (pin "2") (pinfunction "2_2") (pintype "passive"))
      (node (ref "T11") (pin "2") (pinfunction "2_2") (pintype "passive"))
    )
    (net (code "32") (name "/TXRF21_1BB_P") (class "Default")
      (node (ref "MN66") (pin "1") (pinfunction "1_1") (pintype "passive"))
      (node (ref "MN70") (pin "2") (pinfunction "2_2") (pintype "passive"))
      (node (ref "T11") (pin "1") (pinfunction "1_1") (pintype "passive"))
    )
    (net (code "33") (name "/TXRF21_2AB_N") (class "Default")
      (node (ref "IC2") (pin "B10") (pinfunction "pa2on_1_B10") (pintype "passive"))
      (node (ref "MN79") (pin "1") (pinfunction "1_1") (pintype "passive"))
      (node (ref "MN84") (pin "2") (pinfunction "2_2") (pintype "passive"))
      (node (ref "MN88") (pin "2") (pinfunction "2_2") (pintype "passive"))
    )
    (net (code "34") (name "/TXRF21_2AB_P") (class "Default")
      (node (ref "IC2") (pin "A9") (pinfunction "pa2op_1_A9") (pintype "passive"))
      (node (ref "MN80") (pin "1") (pinfunction "1_1") (pintype "passive"))
      (node (ref "MN82") (pin "2") (pinfunction "2_2") (pintype "passive"))
      (node (ref "MN84") (pin "1") (pinfunction "1_1") (pintype "passive"))
    )
    (net (code "35") (name "/TXRF21_2BB_N") (class "Default")
      (node (ref "MN86") (pin "1") (pinfunction "1_1") (pintype "passive"))
      (node (ref "MN88") (pin "1") (pinfunction "1_1") (pintype "passive"))
      (node (ref "T14") (pin "4") (pinfunction "4_4") (pintype "passive"))
    )
    (net (code "36") (name "/TXRF21_2BB_P") (class "Default")
      (node (ref "MN82") (pin "1") (pinfunction "1_1") (pintype "passive"))
      (node (ref "MN86") (pin "2") (pinfunction "2_2") (pintype "passive"))
      (node (ref "T14") (pin "6") (pinfunction "6_6") (pintype "passive"))
    )
    (net (code "37") (name "/TXRF22_1AB_N") (class "Default")
      (node (ref "IC2") (pin "C11") (pinfunction "pa1on_2_C11") (pintype "passive"))
      (node (ref "MN61") (pin "1") (pinfunction "1_1") (pintype "passive"))
      (node (ref "MN67") (pin "1") (pinfunction "1_1") (pintype "passive"))
      (node (ref "MN71") (pin "1") (pinfunction "1_1") (pintype "passive"))
    )
    (net (code "38") (name "/TXRF22_1AB_P") (class "Default")
      (node (ref "IC2") (pin "B12") (pinfunction "pa1op_2_B12") (pintype "passive"))
      (node (ref "MN62") (pin "1") (pinfunction "1_1") (pintype "passive"))
      (node (ref "MN65") (pin "2") (pinfunction "2_2") (pintype "passive"))
      (node (ref "MN67") (pin "2") (pinfunction "2_2") (pintype "passive"))
    )
    (net (code "39") (name "/TXRF22_1BB_N") (class "Default")
      (node (ref "MN68") (pin "1") (pinfunction "1_1") (pintype "passive"))
      (node (ref "MN71") (pin "2") (pinfunction "2_2") (pintype "passive"))
      (node (ref "T12") (pin "2") (pinfunction "2_2") (pintype "passive"))
    )
    (net (code "40") (name "/TXRF22_1BB_P") (class "Default")
      (node (ref "MN65") (pin "1") (pinfunction "1_1") (pintype "passive"))
      (node (ref "MN68") (pin "2") (pinfunction "2_2") (pintype "passive"))
      (node (ref "T12") (pin "1") (pinfunction "1_1") (pintype "passive"))
    )
    (net (code "41") (name "/TXRF22_2AB_N") (class "Default")
      (node (ref "IC2") (pin "B14") (pinfunction "pa2on_2_B14") (pintype "passive"))
      (node (ref "MN77") (pin "1") (pinfunction "1_1") (pintype "passive"))
      (node (ref "MN83") (pin "2") (pinfunction "2_2") (pintype "passive"))
      (node (ref "MN87") (pin "2") (pinfunction "2_2") (pintype "passive"))
    )
    (net (code "42") (name "/TXRF22_2AB_P") (class "Default")
      (node (ref "IC2") (pin "A13") (pinfunction "pa2op_2_A13") (pintype "passive"))
      (node (ref "MN78") (pin "1") (pinfunction "1_1") (pintype "passive"))
      (node (ref "MN81") (pin "2") (pinfunction "2_2") (pintype "passive"))
      (node (ref "MN83") (pin "1") (pinfunction "1_1") (pintype "passive"))
    )
    (net (code "43") (name "/TXRF22_2BB_N") (class "Default")
      (node (ref "MN85") (pin "1") (pinfunction "1_1") (pintype "passive"))
      (node (ref "MN87") (pin "1") (pinfunction "1_1") (pintype "passive"))
      (node (ref "T13") (pin "4") (pinfunction "4_4") (pintype "passive"))
    )
    (net (code "44") (name "/TXRF22_2BB_P") (class "Default")
      (node (ref "MN81") (pin "1") (pinfunction "1_1") (pintype "passive"))
      (node (ref "MN85") (pin "2") (pinfunction "2_2") (pintype "passive"))
      (node (ref "T13") (pin "6") (pinfunction "6_6") (pintype "passive"))
    )
    (net (code "45") (name "GND") (class "Default")
      (node (ref "C29") (pin "1") (pinfunction "1_1") (pintype "passive"))
      (node (ref "C30") (pin "1") (pinfunction "1_1") (pintype "passive"))
      (node (ref "C31") (pin "2") (pinfunction "2_2") (pintype "passive"))
      (node (ref "C32") (pin "2") (pinfunction "2_2") (pintype "passive"))
      (node (ref "C33") (pin "1") (pinfunction "1_1") (pintype "passive"))
      (node (ref "C34") (pin "1") (pinfunction "1_1") (pintype "passive"))
      (node (ref "C35") (pin "2") (pinfunction "2_2") (pintype "passive"))
      (node (ref "C36") (pin "2") (pinfunction "2_2") (pintype "passive"))
      (node (ref "C39") (pin "2") (pinfunction "2_2") (pintype "passive"))
      (node (ref "C40") (pin "1") (pinfunction "1_1") (pintype "passive"))
      (node (ref "C41") (pin "1") (pinfunction "1_1") (pintype "passive"))
      (node (ref "C42") (pin "2") (pinfunction "2_2") (pintype "passive"))
      (node (ref "C43") (pin "2") (pinfunction "2_2") (pintype "passive"))
      (node (ref "C44") (pin "2") (pinfunction "2_2") (pintype "passive"))
      (node (ref "C45") (pin "1") (pinfunction "1_1") (pintype "passive"))
      (node (ref "C46") (pin "1") (pinfunction "1_1") (pintype "passive"))
      (node (ref "ESD10") (pin "2") (pinfunction "2_2") (pintype "passive"))
      (node (ref "ESD11") (pin "2") (pinfunction "2_2") (pintype "passive"))
      (node (ref "ESD12") (pin "2") (pinfunction "2_2") (pintype "passive"))
      (node (ref "ESD7") (pin "2") (pinfunction "2_2") (pintype "passive"))
      (node (ref "ESD8") (pin "2") (pinfunction "2_2") (pintype "passive"))
      (node (ref "ESD9") (pin "2") (pinfunction "2_2") (pintype "passive"))
      (node (ref "IC2") (pin "AJ7") (pinfunction "rfsn_l_RFE_2_AJ7") (pintype "passive"))
      (node (ref "IC2") (pin "AJ9") (pinfunction "rfsp_l_RFE_2_AJ9") (pintype "passive"))
      (node (ref "IC2") (pin "AK12") (pinfunction "rfsn_l_RFE_1_AK12") (pintype "passive"))
      (node (ref "IC2") (pin "AL13") (pinfunction "rfsp_l_RFE_1_AL13") (pintype "passive"))
      (node (ref "J10") (pin "2") (pinfunction "Y_2") (pintype "passive"))
      (node (ref "J11") (pin "2") (pinfunction "Y_2") (pintype "passive"))
      (node (ref "J12") (pin "2") (pinfunction "Y_2") (pintype "passive"))
      (node (ref "J7") (pin "2") (pinfunction "Y_2") (pintype "passive"))
      (node (ref "J8") (pin "2") (pinfunction "Y_2") (pintype "passive"))
      (node (ref "J9") (pin "2") (pinfunction "Y_2") (pintype "passive"))
      (node (ref "T11") (pin "3") (pinfunction "3_3") (pintype "passive"))
      (node (ref "T12") (pin "3") (pinfunction "3_3") (pintype "passive"))
      (node (ref "T13") (pin "3") (pinfunction "3_3") (pintype "passive"))
      (node (ref "T14") (pin "3") (pinfunction "3_3") (pintype "passive"))
      (node (ref "T15") (pin "3") (pinfunction "3_3") (pintype "passive"))
      (node (ref "T16") (pin "3") (pinfunction "3_3") (pintype "passive"))
      (node (ref "T17") (pin "2") (pinfunction "2_2") (pintype "passive"))
      (node (ref "T18") (pin "2") (pinfunction "2_2") (pintype "passive"))
      (node (ref "T19") (pin "3") (pinfunction "3_3") (pintype "passive"))
      (node (ref "T20") (pin "3") (pinfunction "3_3") (pintype "passive"))
    )
    (net (code "46") (name "Net-(C37-Pad2)") (class "Default")
      (node (ref "C37") (pin "2") (pinfunction "2_2") (pintype "passive"))
      (node (ref "T11") (pin "4") (pinfunction "4_4") (pintype "passive"))
    )
    (net (code "47") (name "Net-(C38-Pad2)") (class "Default")
      (node (ref "C38") (pin "2") (pinfunction "2_2") (pintype "passive"))
      (node (ref "T12") (pin "4") (pinfunction "4_4") (pintype "passive"))
    )
    (net (code "48") (name "Net-(C47-Pad2)") (class "Default")
      (node (ref "C47") (pin "2") (pinfunction "2_2") (pintype "passive"))
      (node (ref "T13") (pin "2") (pinfunction "2_2") (pintype "passive"))
    )
    (net (code "49") (name "Net-(C48-Pad2)") (class "Default")
      (node (ref "C48") (pin "2") (pinfunction "2_2") (pintype "passive"))
      (node (ref "T14") (pin "2") (pinfunction "2_2") (pintype "passive"))
    )
    (net (code "50") (name "Net-(C49-Pad2)") (class "Default")
      (node (ref "C49") (pin "2") (pinfunction "2_2") (pintype "passive"))
      (node (ref "T15") (pin "4") (pinfunction "4_4") (pintype "passive"))
    )
    (net (code "51") (name "Net-(C50-Pad2)") (class "Default")
      (node (ref "C50") (pin "2") (pinfunction "2_2") (pintype "passive"))
      (node (ref "T16") (pin "4") (pinfunction "4_4") (pintype "passive"))
    )
    (net (code "52") (name "Net-(C51-Pad2)") (class "Default")
      (node (ref "C51") (pin "2") (pinfunction "2_2") (pintype "passive"))
      (node (ref "T17") (pin "3") (pinfunction "3_3") (pintype "passive"))
    )
    (net (code "53") (name "Net-(C52-Pad2)") (class "Default")
      (node (ref "C52") (pin "2") (pinfunction "2_2") (pintype "passive"))
      (node (ref "T18") (pin "3") (pinfunction "3_3") (pintype "passive"))
    )
    (net (code "54") (name "Net-(C53-Pad2)") (class "Default")
      (node (ref "C53") (pin "2") (pinfunction "2_2") (pintype "passive"))
      (node (ref "T19") (pin "4") (pinfunction "4_4") (pintype "passive"))
    )
    (net (code "55") (name "Net-(C54-Pad2)") (class "Default")
      (node (ref "C54") (pin "2") (pinfunction "2_2") (pintype "passive"))
      (node (ref "T20") (pin "4") (pinfunction "4_4") (pintype "passive"))
    )
    (net (code "56") (name "Net-(J7-X)") (class "Default")
      (node (ref "C37") (pin "1") (pinfunction "1_1") (pintype "passive"))
      (node (ref "ESD7") (pin "1") (pinfunction "1_1") (pintype "passive"))
      (node (ref "J7") (pin "1") (pinfunction "X_1") (pintype "passive"))
    )
    (net (code "57") (name "Net-(J8-X)") (class "Default")
      (node (ref "C38") (pin "1") (pinfunction "1_1") (pintype "passive"))
      (node (ref "ESD8") (pin "1") (pinfunction "1_1") (pintype "passive"))
      (node (ref "J8") (pin "1") (pinfunction "X_1") (pintype "passive"))
    )
    (net (code "58") (name "Net-(J9-X)") (class "Default")
      (node (ref "C49") (pin "1") (pinfunction "1_1") (pintype "passive"))
      (node (ref "ESD9") (pin "1") (pinfunction "1_1") (pintype "passive"))
      (node (ref "J9") (pin "1") (pinfunction "X_1") (pintype "passive"))
    )
    (net (code "59") (name "Net-(J10-X)") (class "Default")
      (node (ref "C50") (pin "1") (pinfunction "1_1") (pintype "passive"))
      (node (ref "ESD10") (pin "1") (pinfunction "1_1") (pintype "passive"))
      (node (ref "J10") (pin "1") (pinfunction "X_1") (pintype "passive"))
    )
    (net (code "60") (name "Net-(J11-X)") (class "Default")
      (node (ref "C53") (pin "1") (pinfunction "1_1") (pintype "passive"))
      (node (ref "ESD11") (pin "1") (pinfunction "1_1") (pintype "passive"))
      (node (ref "J11") (pin "1") (pinfunction "X_1") (pintype "passive"))
    )
    (net (code "61") (name "Net-(J12-X)") (class "Default")
      (node (ref "C54") (pin "1") (pinfunction "1_1") (pintype "passive"))
      (node (ref "ESD12") (pin "1") (pinfunction "1_1") (pintype "passive"))
      (node (ref "J12") (pin "1") (pinfunction "X_1") (pintype "passive"))
    )
    (net (code "62") (name "Net-(MN57-Pad1)") (class "Default")
      (node (ref "MN57") (pin "1") (pinfunction "1_1") (pintype "passive"))
      (node (ref "MN61") (pin "2") (pinfunction "2_2") (pintype "passive"))
    )
    (net (code "63") (name "Net-(MN58-Pad1)") (class "Default")
      (node (ref "MN58") (pin "1") (pinfunction "1_1") (pintype "passive"))
      (node (ref "MN62") (pin "2") (pinfunction "2_2") (pintype "passive"))
    )
    (net (code "64") (name "Net-(MN59-Pad1)") (class "Default")
      (node (ref "MN59") (pin "1") (pinfunction "1_1") (pintype "passive"))
      (node (ref "MN63") (pin "2") (pinfunction "2_2") (pintype "passive"))
    )
    (net (code "65") (name "Net-(MN60-Pad1)") (class "Default")
      (node (ref "MN60") (pin "1") (pinfunction "1_1") (pintype "passive"))
      (node (ref "MN64") (pin "2") (pinfunction "2_2") (pintype "passive"))
    )
    (net (code "66") (name "Net-(MN73-Pad1)") (class "Default")
      (node (ref "MN73") (pin "1") (pinfunction "1_1") (pintype "passive"))
      (node (ref "MN77") (pin "2") (pinfunction "2_2") (pintype "passive"))
    )
    (net (code "67") (name "Net-(MN74-Pad1)") (class "Default")
      (node (ref "MN74") (pin "1") (pinfunction "1_1") (pintype "passive"))
      (node (ref "MN78") (pin "2") (pinfunction "2_2") (pintype "passive"))
    )
    (net (code "68") (name "Net-(MN75-Pad1)") (class "Default")
      (node (ref "MN75") (pin "1") (pinfunction "1_1") (pintype "passive"))
      (node (ref "MN79") (pin "2") (pinfunction "2_2") (pintype "passive"))
    )
    (net (code "69") (name "Net-(MN76-Pad1)") (class "Default")
      (node (ref "MN76") (pin "1") (pinfunction "1_1") (pintype "passive"))
      (node (ref "MN80") (pin "2") (pinfunction "2_2") (pintype "passive"))
    )
    (net (code "70") (name "VCC1P8_LMS2_A") (class "Default")
      (node (ref "C32") (pin "1") (pinfunction "1_1") (pintype "passive"))
      (node (ref "C33") (pin "2") (pinfunction "2_2") (pintype "passive"))
      (node (ref "C34") (pin "2") (pinfunction "2_2") (pintype "passive"))
      (node (ref "C35") (pin "1") (pinfunction "1_1") (pintype "passive"))
      (node (ref "C43") (pin "1") (pinfunction "1_1") (pintype "passive"))
      (node (ref "C44") (pin "1") (pinfunction "1_1") (pintype "passive"))
      (node (ref "C45") (pin "2") (pinfunction "2_2") (pintype "passive"))
      (node (ref "C46") (pin "2") (pinfunction "2_2") (pintype "passive"))
      (node (ref "MN59") (pin "2") (pinfunction "2_2") (pintype "passive"))
      (node (ref "MN60") (pin "2") (pinfunction "2_2") (pintype "passive"))
      (node (ref "MN75") (pin "2") (pinfunction "2_2") (pintype "passive"))
      (node (ref "MN76") (pin "2") (pinfunction "2_2") (pintype "passive"))
    )
    (net (code "71") (name "VCC1P8_LMS2_B") (class "Default")
      (node (ref "C29") (pin "2") (pinfunction "2_2") (pintype "passive"))
      (node (ref "C30") (pin "2") (pinfunction "2_2") (pintype "passive"))
      (node (ref "C31") (pin "1") (pinfunction "1_1") (pintype "passive"))
      (node (ref "C36") (pin "1") (pinfunction "1_1") (pintype "passive"))
      (node (ref "C39") (pin "1") (pinfunction "1_1") (pintype "passive"))
      (node (ref "C40") (pin "2") (pinfunction "2_2") (pintype "passive"))
      (node (ref "C41") (pin "2") (pinfunction "2_2") (pintype "passive"))
      (node (ref "C42") (pin "1") (pinfunction "1_1") (pintype "passive"))
      (node (ref "MN57") (pin "2") (pinfunction "2_2") (pintype "passive"))
      (node (ref "MN58") (pin "2") (pinfunction "2_2") (pintype "passive"))
      (node (ref "MN73") (pin "2") (pinfunction "2_2") (pintype "passive"))
      (node (ref "MN74") (pin "2") (pinfunction "2_2") (pintype "passive"))
    )
  )
)
